# NodeMCU_watering_system.net
KiCad netlist of a schematic drawn in EAGLE
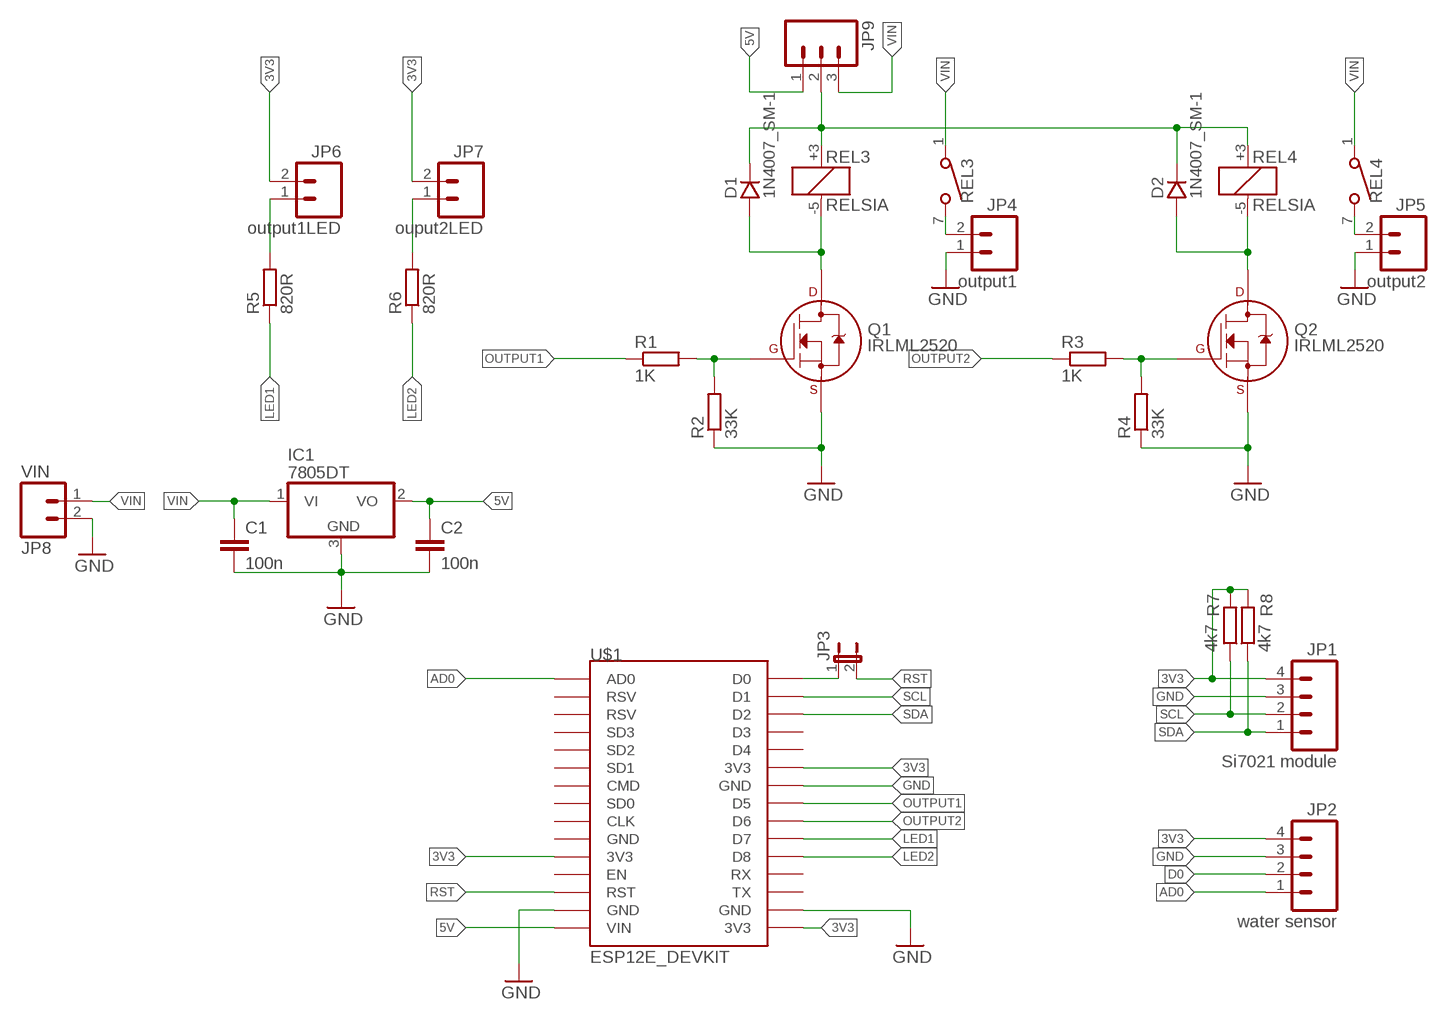
[diagram p0: schematic, sheet 1]

(export (version "E")
  (design (tool "Eeschema 10.0.6"))
  (components
    (comp (ref "C1")
      (value "100n")
      (footprint "eagle-import:C0805K")
      (libsource (lib "eagle-import") (part "C-EUC0805K"))
    )
    (comp (ref "C2")
      (value "100n")
      (footprint "eagle-import:C0805K")
      (libsource (lib "eagle-import") (part "C-EUC0805K"))
    )
    (comp (ref "D1")
      (value "1N4007_SM-1")
      (footprint "eagle-import:SM-1")
      (libsource (lib "eagle-import") (part "1N4007_SM-1"))
    )
    (comp (ref "D2")
      (value "1N4007_SM-1")
      (footprint "eagle-import:SM-1")
      (libsource (lib "eagle-import") (part "1N4007_SM-1"))
    )
    (comp (ref "IC1")
      (value "7805DT")
      (footprint "eagle-import:TO252")
      (libsource (lib "eagle-import") (part "78DT05"))
    )
    (comp (ref "JP1")
      (value "Si7021 module")
      (footprint "eagle-import:1X04_LONGPADS")
      (libsource (lib "eagle-import") (part "M04LONGPADS"))
    )
    (comp (ref "JP2")
      (value "water sensor")
      (footprint "eagle-import:1X04_LONGPADS")
      (libsource (lib "eagle-import") (part "M04LONGPADS"))
    )
    (comp (ref "JP3")
      (value "JP1E")
      (footprint "eagle-import:JP1")
      (libsource (lib "eagle-import") (part "JP1E"))
    )
    (comp (ref "JP4")
      (value "output1")
      (footprint "eagle-import:1X02_LOCK_LONGPADS")
      (libsource (lib "eagle-import") (part "M02LOCK_LONGPADS"))
    )
    (comp (ref "JP5")
      (value "output2")
      (footprint "eagle-import:1X02_LOCK_LONGPADS")
      (libsource (lib "eagle-import") (part "M02LOCK_LONGPADS"))
    )
    (comp (ref "JP6")
      (value "output1LED")
      (footprint "eagle-import:1X02_LOCK_LONGPADS")
      (libsource (lib "eagle-import") (part "M02LOCK_LONGPADS"))
    )
    (comp (ref "JP7")
      (value "ouput2LED")
      (footprint "eagle-import:1X02_LOCK_LONGPADS")
      (libsource (lib "eagle-import") (part "M02LOCK_LONGPADS"))
    )
    (comp (ref "JP8")
      (value "VIN")
      (footprint "eagle-import:1X02_LOCK_LONGPADS")
      (libsource (lib "eagle-import") (part "M02LOCK_LONGPADS"))
    )
    (comp (ref "JP9")
      (value "M03LONGPADS")
      (footprint "eagle-import:1X03_LONGPADS")
      (libsource (lib "eagle-import") (part "M03LONGPADS"))
    )
    (comp (ref "Q1")
      (value "IRLML2520")
      (footprint "eagle-import:SOT-23")
      (libsource (lib "eagle-import") (part "2N700_SOT232A"))
    )
    (comp (ref "Q2")
      (value "IRLML2520")
      (footprint "eagle-import:SOT-23")
      (libsource (lib "eagle-import") (part "2N700_SOT232A"))
    )
    (comp (ref "R1")
      (value "1K")
      (footprint "eagle-import:M0805")
      (libsource (lib "eagle-import") (part "R-EU_M0805"))
    )
    (comp (ref "R2")
      (value "33K")
      (footprint "eagle-import:M0805")
      (libsource (lib "eagle-import") (part "R-EU_M0805"))
    )
    (comp (ref "R3")
      (value "1K")
      (footprint "eagle-import:M0805")
      (libsource (lib "eagle-import") (part "R-EU_M0805"))
    )
    (comp (ref "R4")
      (value "33K")
      (footprint "eagle-import:M0805")
      (libsource (lib "eagle-import") (part "R-EU_M0805"))
    )
    (comp (ref "R5")
      (value "820R")
      (footprint "eagle-import:M0805")
      (libsource (lib "eagle-import") (part "R-EU_M0805"))
    )
    (comp (ref "R6")
      (value "820R")
      (footprint "eagle-import:M0805")
      (libsource (lib "eagle-import") (part "R-EU_M0805"))
    )
    (comp (ref "R7")
      (value "4k7")
      (footprint "eagle-import:M0805")
      (libsource (lib "eagle-import") (part "R-EU_M0805"))
    )
    (comp (ref "R8")
      (value "4k7")
      (footprint "eagle-import:M0805")
      (libsource (lib "eagle-import") (part "R-EU_M0805"))
    )
    (comp (ref "REL3")
      (value "RELSIA")
      (footprint "eagle-import:RELSIA")
      (libsource (lib "eagle-import") (part "RELSIA??"))
    )
    (comp (ref "REL4")
      (value "RELSIA")
      (footprint "eagle-import:RELSIA")
      (libsource (lib "eagle-import") (part "RELSIA??"))
    )
    (comp (ref "U$1")
      (value "ESP12E_DEVKIT")
      (footprint "eagle-import:ESP12E_DEVKIT")
      (libsource (lib "eagle-import") (part "ESP12E_DEVKIT"))
    )
  )
  (nets
    (net (code "1") (name "3V3") (class "Default")
      (node (ref "JP1") (pin "4") (pinfunction "4_4") (pintype "passive"))
      (node (ref "JP2") (pin "4") (pinfunction "4_4") (pintype "passive"))
      (node (ref "JP6") (pin "2") (pinfunction "2_2") (pintype "passive"))
      (node (ref "JP7") (pin "2") (pinfunction "2_2") (pintype "passive"))
      (node (ref "R7") (pin "2") (pinfunction "2_2") (pintype "passive"))
      (node (ref "R8") (pin "2") (pinfunction "2_2") (pintype "passive"))
      (node (ref "U$1") (pin "3V3@0") (pinfunction "3V3_3V3@0") (pintype "bidirectional"))
      (node (ref "U$1") (pin "3V3@1") (pinfunction "3V3_3V3@1") (pintype "bidirectional"))
      (node (ref "U$1") (pin "3V3@2") (pinfunction "3V3_3V3@2") (pintype "bidirectional"))
    )
    (net (code "2") (name "5V") (class "Default")
      (node (ref "C2") (pin "1") (pinfunction "1_1") (pintype "passive"))
      (node (ref "IC1") (pin "2") (pinfunction "VO_2") (pintype "passive"))
      (node (ref "JP9") (pin "1") (pinfunction "1_1") (pintype "passive"))
      (node (ref "U$1") (pin "VIN") (pinfunction "VIN_VIN") (pintype "bidirectional"))
    )
    (net (code "3") (name "AD0") (class "Default")
      (node (ref "JP2") (pin "1") (pinfunction "1_1") (pintype "passive"))
      (node (ref "U$1") (pin "AD0") (pinfunction "AD0_AD0") (pintype "bidirectional"))
    )
    (net (code "4") (name "D0") (class "Default")
      (node (ref "JP2") (pin "2") (pinfunction "2_2") (pintype "passive"))
    )
    (net (code "5") (name "GND") (class "Default")
      (node (ref "C1") (pin "2") (pinfunction "2_2") (pintype "passive"))
      (node (ref "C2") (pin "2") (pinfunction "2_2") (pintype "passive"))
      (node (ref "IC1") (pin "3") (pinfunction "GND_3") (pintype "passive"))
      (node (ref "JP1") (pin "3") (pinfunction "3_3") (pintype "passive"))
      (node (ref "JP2") (pin "3") (pinfunction "3_3") (pintype "passive"))
      (node (ref "JP4") (pin "1") (pinfunction "1_1") (pintype "passive"))
      (node (ref "JP5") (pin "1") (pinfunction "1_1") (pintype "passive"))
      (node (ref "JP8") (pin "2") (pinfunction "2_2") (pintype "passive"))
      (node (ref "Q1") (pin "2") (pinfunction "S_2") (pintype "bidirectional"))
      (node (ref "Q2") (pin "2") (pinfunction "S_2") (pintype "bidirectional"))
      (node (ref "R2") (pin "1") (pinfunction "1_1") (pintype "passive"))
      (node (ref "R4") (pin "1") (pinfunction "1_1") (pintype "passive"))
      (node (ref "U$1") (pin "GND@1") (pinfunction "GND_GND@1") (pintype "bidirectional"))
      (node (ref "U$1") (pin "GND@2") (pinfunction "GND_GND@2") (pintype "bidirectional"))
      (node (ref "U$1") (pin "GND@3") (pinfunction "GND_GND@3") (pintype "bidirectional"))
    )
    (net (code "6") (name "LED1") (class "Default")
      (node (ref "R5") (pin "1") (pinfunction "1_1") (pintype "passive"))
      (node (ref "U$1") (pin "D7") (pinfunction "D7_D7") (pintype "bidirectional"))
    )
    (net (code "7") (name "LED2") (class "Default")
      (node (ref "R6") (pin "1") (pinfunction "1_1") (pintype "passive"))
      (node (ref "U$1") (pin "D8") (pinfunction "D8_D8") (pintype "bidirectional"))
    )
    (net (code "8") (name "Net-(JP3-Pad1)") (class "Default")
      (node (ref "JP3") (pin "1") (pinfunction "1_1") (pintype "passive"))
      (node (ref "U$1") (pin "D0") (pinfunction "D0_D0") (pintype "bidirectional"))
    )
    (net (code "9") (name "Net-(JP6-Pad1)") (class "Default")
      (node (ref "JP6") (pin "1") (pinfunction "1_1") (pintype "passive"))
      (node (ref "R5") (pin "2") (pinfunction "2_2") (pintype "passive"))
    )
    (net (code "10") (name "Net-(JP7-Pad1)") (class "Default")
      (node (ref "JP7") (pin "1") (pinfunction "1_1") (pintype "passive"))
      (node (ref "R6") (pin "2") (pinfunction "2_2") (pintype "passive"))
    )
    (net (code "11") (name "Net-(Q1-D)") (class "Default")
      (node (ref "D1") (pin "A") (pinfunction "A_A") (pintype "passive"))
      (node (ref "Q1") (pin "3") (pinfunction "D_3") (pintype "bidirectional"))
      (node (ref "REL3") (pin "-5") (pinfunction "C-_-5") (pintype "passive"))
    )
    (net (code "12") (name "Net-(Q1-G)") (class "Default")
      (node (ref "Q1") (pin "1") (pinfunction "G_1") (pintype "tri_state"))
      (node (ref "R1") (pin "2") (pinfunction "2_2") (pintype "passive"))
      (node (ref "R2") (pin "2") (pinfunction "2_2") (pintype "passive"))
    )
    (net (code "13") (name "Net-(Q2-D)") (class "Default")
      (node (ref "D2") (pin "A") (pinfunction "A_A") (pintype "passive"))
      (node (ref "Q2") (pin "3") (pinfunction "D_3") (pintype "bidirectional"))
      (node (ref "REL4") (pin "-5") (pinfunction "C-_-5") (pintype "passive"))
    )
    (net (code "14") (name "Net-(Q2-G)") (class "Default")
      (node (ref "Q2") (pin "1") (pinfunction "G_1") (pintype "tri_state"))
      (node (ref "R3") (pin "2") (pinfunction "2_2") (pintype "passive"))
      (node (ref "R4") (pin "2") (pinfunction "2_2") (pintype "passive"))
    )
    (net (code "15") (name "Net-(REL3A-C+)") (class "Default")
      (node (ref "D1") (pin "K") (pinfunction "K_K") (pintype "passive"))
      (node (ref "D2") (pin "K") (pinfunction "K_K") (pintype "passive"))
      (node (ref "JP9") (pin "2") (pinfunction "2_2") (pintype "passive"))
      (node (ref "REL3") (pin "+3") (pinfunction "C+_+3") (pintype "passive"))
      (node (ref "REL4") (pin "+3") (pinfunction "C+_+3") (pintype "passive"))
    )
    (net (code "16") (name "Net-(REL3B-2)") (class "Default")
      (node (ref "JP4") (pin "2") (pinfunction "2_2") (pintype "passive"))
      (node (ref "REL3") (pin "7") (pinfunction "2_7") (pintype "passive"))
    )
    (net (code "17") (name "Net-(REL4B-2)") (class "Default")
      (node (ref "JP5") (pin "2") (pinfunction "2_2") (pintype "passive"))
      (node (ref "REL4") (pin "7") (pinfunction "2_7") (pintype "passive"))
    )
    (net (code "18") (name "OUTPUT1") (class "Default")
      (node (ref "R1") (pin "1") (pinfunction "1_1") (pintype "passive"))
      (node (ref "U$1") (pin "D5") (pinfunction "D5_D5") (pintype "bidirectional"))
    )
    (net (code "19") (name "OUTPUT2") (class "Default")
      (node (ref "R3") (pin "1") (pinfunction "1_1") (pintype "passive"))
      (node (ref "U$1") (pin "D6") (pinfunction "D6_D6") (pintype "bidirectional"))
    )
    (net (code "20") (name "RST") (class "Default")
      (node (ref "JP3") (pin "2") (pinfunction "2_2") (pintype "passive"))
      (node (ref "U$1") (pin "RST") (pinfunction "RST_RST") (pintype "bidirectional"))
    )
    (net (code "21") (name "SCL") (class "Default")
      (node (ref "JP1") (pin "2") (pinfunction "2_2") (pintype "passive"))
      (node (ref "R7") (pin "1") (pinfunction "1_1") (pintype "passive"))
      (node (ref "U$1") (pin "D1") (pinfunction "D1_D1") (pintype "bidirectional"))
    )
    (net (code "22") (name "SDA") (class "Default")
      (node (ref "JP1") (pin "1") (pinfunction "1_1") (pintype "passive"))
      (node (ref "R8") (pin "1") (pinfunction "1_1") (pintype "passive"))
      (node (ref "U$1") (pin "D2") (pinfunction "D2_D2") (pintype "bidirectional"))
    )
    (net (code "23") (name "VIN") (class "Default")
      (node (ref "C1") (pin "1") (pinfunction "1_1") (pintype "passive"))
      (node (ref "IC1") (pin "1") (pinfunction "VI_1") (pintype "input"))
      (node (ref "JP8") (pin "1") (pinfunction "1_1") (pintype "passive"))
      (node (ref "JP9") (pin "3") (pinfunction "3_3") (pintype "passive"))
      (node (ref "REL3") (pin "1") (pinfunction "1_1") (pintype "passive"))
      (node (ref "REL4") (pin "1") (pinfunction "1_1") (pintype "passive"))
    )
    (net (code "24") (name "unconnected-(U$1-GND-PadGND@0)") (class "Default")
      (node (ref "U$1") (pin "GND@0") (pinfunction "GND_GND@0") (pintype "bidirectional"))
    )
    (net (code "25") (name "unconnected-(U$1-PadCLK)") (class "Default")
      (node (ref "U$1") (pin "CLK") (pinfunction "CLK_CLK") (pintype "bidirectional"))
    )
    (net (code "26") (name "unconnected-(U$1-PadCMD)") (class "Default")
      (node (ref "U$1") (pin "CMD") (pinfunction "CMD_CMD") (pintype "bidirectional"))
    )
    (net (code "27") (name "unconnected-(U$1-PadD3)") (class "Default")
      (node (ref "U$1") (pin "D3") (pinfunction "D3_D3") (pintype "bidirectional"))
    )
    (net (code "28") (name "unconnected-(U$1-PadD4)") (class "Default")
      (node (ref "U$1") (pin "D4") (pinfunction "D4_D4") (pintype "bidirectional"))
    )
    (net (code "29") (name "unconnected-(U$1-PadEN)") (class "Default")
      (node (ref "U$1") (pin "EN") (pinfunction "EN_EN") (pintype "bidirectional"))
    )
    (net (code "30") (name "unconnected-(U$1-PadRX)") (class "Default")
      (node (ref "U$1") (pin "RX") (pinfunction "RX_RX") (pintype "bidirectional"))
    )
    (net (code "31") (name "unconnected-(U$1-PadSD0)") (class "Default")
      (node (ref "U$1") (pin "SD0") (pinfunction "SD0_SD0") (pintype "bidirectional"))
    )
    (net (code "32") (name "unconnected-(U$1-PadSD1)") (class "Default")
      (node (ref "U$1") (pin "SD1") (pinfunction "SD1_SD1") (pintype "bidirectional"))
    )
    (net (code "33") (name "unconnected-(U$1-PadSD2)") (class "Default")
      (node (ref "U$1") (pin "SD2") (pinfunction "SD2_SD2") (pintype "bidirectional"))
    )
    (net (code "34") (name "unconnected-(U$1-PadSD3)") (class "Default")
      (node (ref "U$1") (pin "SD3") (pinfunction "SD3_SD3") (pintype "bidirectional"))
    )
    (net (code "35") (name "unconnected-(U$1-PadTX)") (class "Default")
      (node (ref "U$1") (pin "TX") (pinfunction "TX_TX") (pintype "bidirectional"))
    )
    (net (code "36") (name "unconnected-(U$1-RSV-PadRSV@0)") (class "Default")
      (node (ref "U$1") (pin "RSV@0") (pinfunction "RSV_RSV@0") (pintype "bidirectional"))
    )
    (net (code "37") (name "unconnected-(U$1-RSV-PadRSV@1)") (class "Default")
      (node (ref "U$1") (pin "RSV@1") (pinfunction "RSV_RSV@1") (pintype "bidirectional"))
    )
  )
)
